# SWD_adapter.net
KiCad netlist of a schematic drawn in Altium Designer
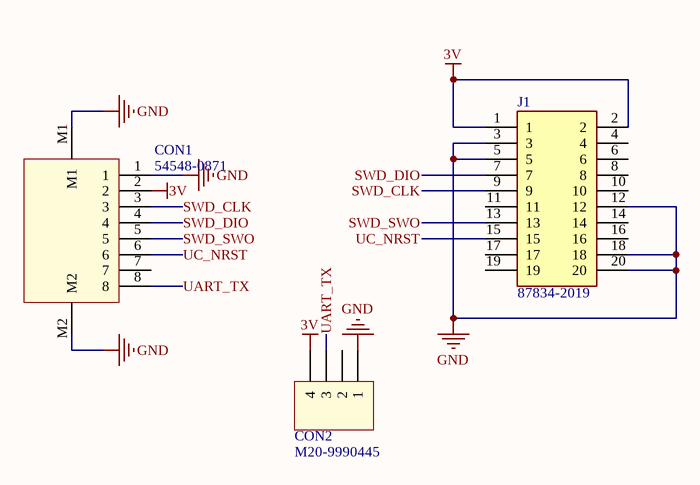
[diagram p0: SWD adapter.SchDoc]

(export (version "E")
  (design (tool "Eeschema 10.0.6"))
  (components
    (comp (ref "CON1")
      (value "54548-0871")
      (footprint "54548-0871")
      (description "Connecteur FFC/FPC, Right-Angle, Surface Mount, ZIF, Bottom Contact\r\nStyle, 30 Circuits")
      (libsource (lib "ConnecteurAutre") (part "54548-0871"))
    )
    (comp (ref "CON2")
      (value "M20-9990445")
      (footprint "M20-9990445")
      (description "4 pins RA 2.54mm droit")
      (libsource (lib "ConnecteurAutre") (part "M20-9990445"))
    )
    (comp (ref "J1")
      (value "87834-2019")
      (footprint "87834-2019")
      (description "Embase PCB, 2.54mm,20 contacts, 2 rangées, traversant")
      (libsource (lib "ConnecteurAutre") (part "87834-2019"))
    )
  )
  (nets
    (net (code "1") (name "/SWD_CLK") (class "Default")
      (node (ref "CON1") (pin "3") (pinfunction "3_3") (pintype "power_in"))
      (node (ref "J1") (pin "9") (pinfunction "9_9") (pintype "passive"))
    )
    (net (code "2") (name "/SWD_DIO") (class "Default")
      (node (ref "CON1") (pin "4") (pinfunction "4_4") (pintype "power_in"))
      (node (ref "J1") (pin "7") (pinfunction "7_7") (pintype "passive"))
    )
    (net (code "3") (name "/SWD_SWO") (class "Default")
      (node (ref "CON1") (pin "5") (pinfunction "5_5") (pintype "power_in"))
      (node (ref "J1") (pin "13") (pinfunction "13_13") (pintype "passive"))
    )
    (net (code "4") (name "/UART_TX") (class "Default")
      (node (ref "CON1") (pin "8") (pinfunction "8_8") (pintype "power_in"))
      (node (ref "CON2") (pin "3") (pinfunction "3_3") (pintype "passive"))
    )
    (net (code "5") (name "/UC_NRST") (class "Default")
      (node (ref "CON1") (pin "6") (pinfunction "6_6") (pintype "power_in"))
      (node (ref "J1") (pin "15") (pinfunction "15_15") (pintype "passive"))
    )
    (net (code "6") (name "3V") (class "Default")
      (node (ref "CON1") (pin "2") (pinfunction "2_2") (pintype "power_in"))
      (node (ref "CON2") (pin "4") (pinfunction "4_4") (pintype "passive"))
      (node (ref "J1") (pin "1") (pinfunction "1_1") (pintype "passive"))
      (node (ref "J1") (pin "2") (pinfunction "2_2") (pintype "passive"))
    )
    (net (code "7") (name "GND") (class "Default")
      (node (ref "CON1") (pin "1") (pinfunction "1_1") (pintype "power_in"))
      (node (ref "CON1") (pin "M1") (pinfunction "M1_M1") (pintype "power_in"))
      (node (ref "CON1") (pin "M2") (pinfunction "M2_M2") (pintype "power_in"))
      (node (ref "CON2") (pin "1") (pinfunction "1_1") (pintype "passive"))
      (node (ref "J1") (pin "12") (pinfunction "12_12") (pintype "passive"))
      (node (ref "J1") (pin "18") (pinfunction "18_18") (pintype "passive"))
      (node (ref "J1") (pin "20") (pinfunction "20_20") (pintype "passive"))
      (node (ref "J1") (pin "3") (pinfunction "3_3") (pintype "passive"))
      (node (ref "J1") (pin "5") (pinfunction "5_5") (pintype "passive"))
    )
    (net (code "8") (name "unconnected-(CON1-Pad7)") (class "Default")
      (node (ref "CON1") (pin "7") (pinfunction "7_7") (pintype "power_in"))
    )
    (net (code "9") (name "unconnected-(CON2-Pad2)") (class "Default")
      (node (ref "CON2") (pin "2") (pinfunction "2_2") (pintype "passive"))
    )
    (net (code "10") (name "unconnected-(J1-Pad4)") (class "Default")
      (node (ref "J1") (pin "4") (pinfunction "4_4") (pintype "passive"))
    )
    (net (code "11") (name "unconnected-(J1-Pad6)") (class "Default")
      (node (ref "J1") (pin "6") (pinfunction "6_6") (pintype "passive"))
    )
    (net (code "12") (name "unconnected-(J1-Pad8)") (class "Default")
      (node (ref "J1") (pin "8") (pinfunction "8_8") (pintype "passive"))
    )
    (net (code "13") (name "unconnected-(J1-Pad10)") (class "Default")
      (node (ref "J1") (pin "10") (pinfunction "10_10") (pintype "passive"))
    )
    (net (code "14") (name "unconnected-(J1-Pad11)") (class "Default")
      (node (ref "J1") (pin "11") (pinfunction "11_11") (pintype "passive"))
    )
    (net (code "15") (name "unconnected-(J1-Pad14)") (class "Default")
      (node (ref "J1") (pin "14") (pinfunction "14_14") (pintype "passive"))
    )
    (net (code "16") (name "unconnected-(J1-Pad16)") (class "Default")
      (node (ref "J1") (pin "16") (pinfunction "16_16") (pintype "passive"))
    )
    (net (code "17") (name "unconnected-(J1-Pad17)") (class "Default")
      (node (ref "J1") (pin "17") (pinfunction "17_17") (pintype "passive"))
    )
    (net (code "18") (name "unconnected-(J1-Pad19)") (class "Default")
      (node (ref "J1") (pin "19") (pinfunction "19_19") (pintype "passive"))
    )
  )
)
